# axiom_beta_plugin_module_3xPMOD.net
KiCad netlist of a schematic drawn in EAGLE
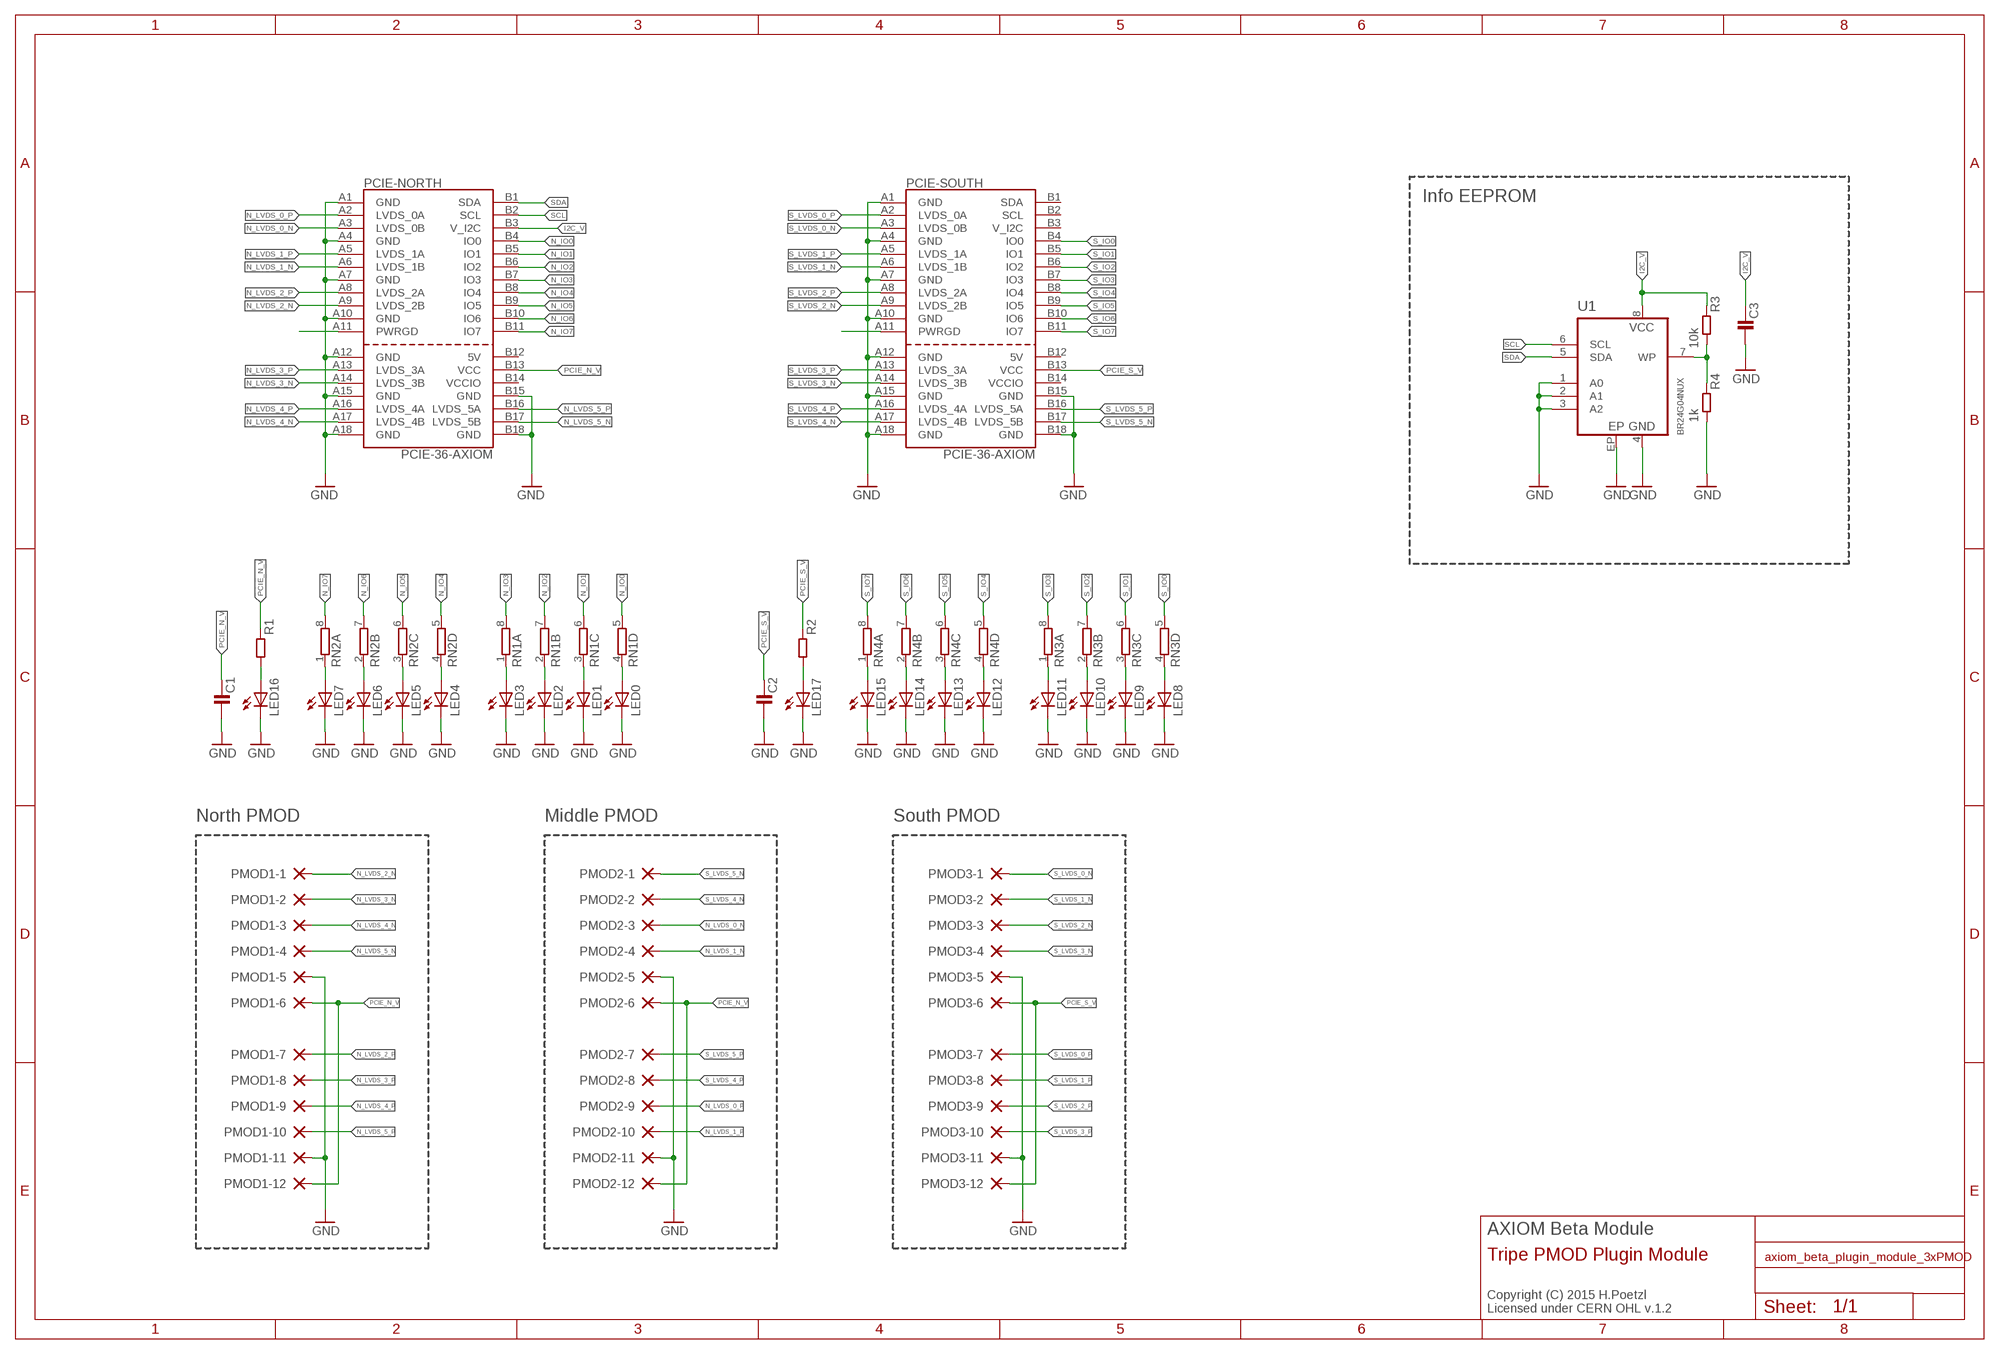
[diagram p0: schematic, sheet 1]

(export (version "E")
  (design (tool "Eeschema 10.0.6"))
  (components
    (comp (ref "C1")
      (value "C1206-A")
      (footprint "eagle-import:1206-A")
      (libsource (lib "eagle-import") (part "C1206-A"))
    )
    (comp (ref "C2")
      (value "C1206-A")
      (footprint "eagle-import:1206-A")
      (libsource (lib "eagle-import") (part "C1206-A"))
    )
    (comp (ref "C3")
      (value "C0402-B")
      (footprint "eagle-import:0402-B")
      (libsource (lib "eagle-import") (part "C0402-B"))
    )
    (comp (ref "LED0")
      (value "LEDCHIPLED_0603")
      (footprint "eagle-import:CHIPLED_0603")
      (libsource (lib "eagle-import") (part "LEDCHIPLED_0603"))
    )
    (comp (ref "LED1")
      (value "LEDCHIPLED_0603")
      (footprint "eagle-import:CHIPLED_0603")
      (libsource (lib "eagle-import") (part "LEDCHIPLED_0603"))
    )
    (comp (ref "LED2")
      (value "LEDCHIPLED_0603")
      (footprint "eagle-import:CHIPLED_0603")
      (libsource (lib "eagle-import") (part "LEDCHIPLED_0603"))
    )
    (comp (ref "LED3")
      (value "LEDCHIPLED_0603")
      (footprint "eagle-import:CHIPLED_0603")
      (libsource (lib "eagle-import") (part "LEDCHIPLED_0603"))
    )
    (comp (ref "LED4")
      (value "LEDCHIPLED_0603")
      (footprint "eagle-import:CHIPLED_0603")
      (libsource (lib "eagle-import") (part "LEDCHIPLED_0603"))
    )
    (comp (ref "LED5")
      (value "LEDCHIPLED_0603")
      (footprint "eagle-import:CHIPLED_0603")
      (libsource (lib "eagle-import") (part "LEDCHIPLED_0603"))
    )
    (comp (ref "LED6")
      (value "LEDCHIPLED_0603")
      (footprint "eagle-import:CHIPLED_0603")
      (libsource (lib "eagle-import") (part "LEDCHIPLED_0603"))
    )
    (comp (ref "LED7")
      (value "LEDCHIPLED_0603")
      (footprint "eagle-import:CHIPLED_0603")
      (libsource (lib "eagle-import") (part "LEDCHIPLED_0603"))
    )
    (comp (ref "LED8")
      (value "LEDCHIPLED_0603")
      (footprint "eagle-import:CHIPLED_0603")
      (libsource (lib "eagle-import") (part "LEDCHIPLED_0603"))
    )
    (comp (ref "LED9")
      (value "LEDCHIPLED_0603")
      (footprint "eagle-import:CHIPLED_0603")
      (libsource (lib "eagle-import") (part "LEDCHIPLED_0603"))
    )
    (comp (ref "LED10")
      (value "LEDCHIPLED_0603")
      (footprint "eagle-import:CHIPLED_0603")
      (libsource (lib "eagle-import") (part "LEDCHIPLED_0603"))
    )
    (comp (ref "LED11")
      (value "LEDCHIPLED_0603")
      (footprint "eagle-import:CHIPLED_0603")
      (libsource (lib "eagle-import") (part "LEDCHIPLED_0603"))
    )
    (comp (ref "LED12")
      (value "LEDCHIPLED_0603")
      (footprint "eagle-import:CHIPLED_0603")
      (libsource (lib "eagle-import") (part "LEDCHIPLED_0603"))
    )
    (comp (ref "LED13")
      (value "LEDCHIPLED_0603")
      (footprint "eagle-import:CHIPLED_0603")
      (libsource (lib "eagle-import") (part "LEDCHIPLED_0603"))
    )
    (comp (ref "LED14")
      (value "LEDCHIPLED_0603")
      (footprint "eagle-import:CHIPLED_0603")
      (libsource (lib "eagle-import") (part "LEDCHIPLED_0603"))
    )
    (comp (ref "LED15")
      (value "LEDCHIPLED_0603")
      (footprint "eagle-import:CHIPLED_0603")
      (libsource (lib "eagle-import") (part "LEDCHIPLED_0603"))
    )
    (comp (ref "LED16")
      (value "LEDCHIPLED_0603")
      (footprint "eagle-import:CHIPLED_0603")
      (libsource (lib "eagle-import") (part "LEDCHIPLED_0603"))
    )
    (comp (ref "LED17")
      (value "LEDCHIPLED_0603")
      (footprint "eagle-import:CHIPLED_0603")
      (libsource (lib "eagle-import") (part "LEDCHIPLED_0603"))
    )
    (comp (ref "PCIE-NORTH")
      (value "PCIE-36-AXIOM")
      (footprint "eagle-import:PCIE-36-AXIOM")
      (libsource (lib "eagle-import") (part "PCIE-36-AXIOM"))
    )
    (comp (ref "PCIE-SOUTH")
      (value "PCIE-36-AXIOM")
      (footprint "eagle-import:PCIE-36-AXIOM")
      (libsource (lib "eagle-import") (part "PCIE-36-AXIOM"))
    )
    (comp (ref "PMOD1-1")
      (value "SMD-PAD1.6X3.8MM-U")
      (footprint "eagle-import:1.6X3.8U-MM")
      (libsource (lib "eagle-import") (part "SMD-PAD1.6X3.8MM-U"))
    )
    (comp (ref "PMOD1-2")
      (value "SMD-PAD1.6X3.8MM-U")
      (footprint "eagle-import:1.6X3.8U-MM")
      (libsource (lib "eagle-import") (part "SMD-PAD1.6X3.8MM-U"))
    )
    (comp (ref "PMOD1-3")
      (value "SMD-PAD1.6X3.8MM-U")
      (footprint "eagle-import:1.6X3.8U-MM")
      (libsource (lib "eagle-import") (part "SMD-PAD1.6X3.8MM-U"))
    )
    (comp (ref "PMOD1-4")
      (value "SMD-PAD1.6X3.8MM-U")
      (footprint "eagle-import:1.6X3.8U-MM")
      (libsource (lib "eagle-import") (part "SMD-PAD1.6X3.8MM-U"))
    )
    (comp (ref "PMOD1-5")
      (value "SMD-PAD1.6X3.8MM-U")
      (footprint "eagle-import:1.6X3.8U-MM")
      (libsource (lib "eagle-import") (part "SMD-PAD1.6X3.8MM-U"))
    )
    (comp (ref "PMOD1-6")
      (value "SMD-PAD1.6X3.8MM-U")
      (footprint "eagle-import:1.6X3.8U-MM")
      (libsource (lib "eagle-import") (part "SMD-PAD1.6X3.8MM-U"))
    )
    (comp (ref "PMOD1-7")
      (value "SMD-PAD1.6X3.8MM-U")
      (footprint "eagle-import:1.6X3.8U-MM")
      (libsource (lib "eagle-import") (part "SMD-PAD1.6X3.8MM-U"))
    )
    (comp (ref "PMOD1-8")
      (value "SMD-PAD1.6X3.8MM-U")
      (footprint "eagle-import:1.6X3.8U-MM")
      (libsource (lib "eagle-import") (part "SMD-PAD1.6X3.8MM-U"))
    )
    (comp (ref "PMOD1-9")
      (value "SMD-PAD1.6X3.8MM-U")
      (footprint "eagle-import:1.6X3.8U-MM")
      (libsource (lib "eagle-import") (part "SMD-PAD1.6X3.8MM-U"))
    )
    (comp (ref "PMOD1-10")
      (value "SMD-PAD1.6X3.8MM-U")
      (footprint "eagle-import:1.6X3.8U-MM")
      (libsource (lib "eagle-import") (part "SMD-PAD1.6X3.8MM-U"))
    )
    (comp (ref "PMOD1-11")
      (value "SMD-PAD1.6X3.8MM-U")
      (footprint "eagle-import:1.6X3.8U-MM")
      (libsource (lib "eagle-import") (part "SMD-PAD1.6X3.8MM-U"))
    )
    (comp (ref "PMOD1-12")
      (value "SMD-PAD1.6X3.8MM-U")
      (footprint "eagle-import:1.6X3.8U-MM")
      (libsource (lib "eagle-import") (part "SMD-PAD1.6X3.8MM-U"))
    )
    (comp (ref "PMOD2-1")
      (value "SMD-PAD1.6X3.8MM-U")
      (footprint "eagle-import:1.6X3.8U-MM")
      (libsource (lib "eagle-import") (part "SMD-PAD1.6X3.8MM-U"))
    )
    (comp (ref "PMOD2-2")
      (value "SMD-PAD1.6X3.8MM-U")
      (footprint "eagle-import:1.6X3.8U-MM")
      (libsource (lib "eagle-import") (part "SMD-PAD1.6X3.8MM-U"))
    )
    (comp (ref "PMOD2-3")
      (value "SMD-PAD1.6X3.8MM-U")
      (footprint "eagle-import:1.6X3.8U-MM")
      (libsource (lib "eagle-import") (part "SMD-PAD1.6X3.8MM-U"))
    )
    (comp (ref "PMOD2-4")
      (value "SMD-PAD1.6X3.8MM-U")
      (footprint "eagle-import:1.6X3.8U-MM")
      (libsource (lib "eagle-import") (part "SMD-PAD1.6X3.8MM-U"))
    )
    (comp (ref "PMOD2-5")
      (value "SMD-PAD1.6X3.8MM-U")
      (footprint "eagle-import:1.6X3.8U-MM")
      (libsource (lib "eagle-import") (part "SMD-PAD1.6X3.8MM-U"))
    )
    (comp (ref "PMOD2-6")
      (value "SMD-PAD1.6X3.8MM-U")
      (footprint "eagle-import:1.6X3.8U-MM")
      (libsource (lib "eagle-import") (part "SMD-PAD1.6X3.8MM-U"))
    )
    (comp (ref "PMOD2-7")
      (value "SMD-PAD1.6X3.8MM-U")
      (footprint "eagle-import:1.6X3.8U-MM")
      (libsource (lib "eagle-import") (part "SMD-PAD1.6X3.8MM-U"))
    )
    (comp (ref "PMOD2-8")
      (value "SMD-PAD1.6X3.8MM-U")
      (footprint "eagle-import:1.6X3.8U-MM")
      (libsource (lib "eagle-import") (part "SMD-PAD1.6X3.8MM-U"))
    )
    (comp (ref "PMOD2-9")
      (value "SMD-PAD1.6X3.8MM-U")
      (footprint "eagle-import:1.6X3.8U-MM")
      (libsource (lib "eagle-import") (part "SMD-PAD1.6X3.8MM-U"))
    )
    (comp (ref "PMOD2-10")
      (value "SMD-PAD1.6X3.8MM-U")
      (footprint "eagle-import:1.6X3.8U-MM")
      (libsource (lib "eagle-import") (part "SMD-PAD1.6X3.8MM-U"))
    )
    (comp (ref "PMOD2-11")
      (value "SMD-PAD1.6X3.8MM-U")
      (footprint "eagle-import:1.6X3.8U-MM")
      (libsource (lib "eagle-import") (part "SMD-PAD1.6X3.8MM-U"))
    )
    (comp (ref "PMOD2-12")
      (value "SMD-PAD1.6X3.8MM-U")
      (footprint "eagle-import:1.6X3.8U-MM")
      (libsource (lib "eagle-import") (part "SMD-PAD1.6X3.8MM-U"))
    )
    (comp (ref "PMOD3-1")
      (value "SMD-PAD1.6X3.8MM-U")
      (footprint "eagle-import:1.6X3.8U-MM")
      (libsource (lib "eagle-import") (part "SMD-PAD1.6X3.8MM-U"))
    )
    (comp (ref "PMOD3-2")
      (value "SMD-PAD1.6X3.8MM-U")
      (footprint "eagle-import:1.6X3.8U-MM")
      (libsource (lib "eagle-import") (part "SMD-PAD1.6X3.8MM-U"))
    )
    (comp (ref "PMOD3-3")
      (value "SMD-PAD1.6X3.8MM-U")
      (footprint "eagle-import:1.6X3.8U-MM")
      (libsource (lib "eagle-import") (part "SMD-PAD1.6X3.8MM-U"))
    )
    (comp (ref "PMOD3-4")
      (value "SMD-PAD1.6X3.8MM-U")
      (footprint "eagle-import:1.6X3.8U-MM")
      (libsource (lib "eagle-import") (part "SMD-PAD1.6X3.8MM-U"))
    )
    (comp (ref "PMOD3-5")
      (value "SMD-PAD1.6X3.8MM-U")
      (footprint "eagle-import:1.6X3.8U-MM")
      (libsource (lib "eagle-import") (part "SMD-PAD1.6X3.8MM-U"))
    )
    (comp (ref "PMOD3-6")
      (value "SMD-PAD1.6X3.8MM-U")
      (footprint "eagle-import:1.6X3.8U-MM")
      (libsource (lib "eagle-import") (part "SMD-PAD1.6X3.8MM-U"))
    )
    (comp (ref "PMOD3-7")
      (value "SMD-PAD1.6X3.8MM-U")
      (footprint "eagle-import:1.6X3.8U-MM")
      (libsource (lib "eagle-import") (part "SMD-PAD1.6X3.8MM-U"))
    )
    (comp (ref "PMOD3-8")
      (value "SMD-PAD1.6X3.8MM-U")
      (footprint "eagle-import:1.6X3.8U-MM")
      (libsource (lib "eagle-import") (part "SMD-PAD1.6X3.8MM-U"))
    )
    (comp (ref "PMOD3-9")
      (value "SMD-PAD1.6X3.8MM-U")
      (footprint "eagle-import:1.6X3.8U-MM")
      (libsource (lib "eagle-import") (part "SMD-PAD1.6X3.8MM-U"))
    )
    (comp (ref "PMOD3-10")
      (value "SMD-PAD1.6X3.8MM-U")
      (footprint "eagle-import:1.6X3.8U-MM")
      (libsource (lib "eagle-import") (part "SMD-PAD1.6X3.8MM-U"))
    )
    (comp (ref "PMOD3-11")
      (value "SMD-PAD1.6X3.8MM-U")
      (footprint "eagle-import:1.6X3.8U-MM")
      (libsource (lib "eagle-import") (part "SMD-PAD1.6X3.8MM-U"))
    )
    (comp (ref "PMOD3-12")
      (value "SMD-PAD1.6X3.8MM-U")
      (footprint "eagle-import:1.6X3.8U-MM")
      (libsource (lib "eagle-import") (part "SMD-PAD1.6X3.8MM-U"))
    )
    (comp (ref "R1")
      (value "R0402-B")
      (footprint "eagle-import:0402-B")
      (libsource (lib "eagle-import") (part "R0402-B"))
    )
    (comp (ref "R2")
      (value "R0402-B")
      (footprint "eagle-import:0402-B")
      (libsource (lib "eagle-import") (part "R0402-B"))
    )
    (comp (ref "R3")
      (value "10k")
      (footprint "eagle-import:0402-B")
      (libsource (lib "eagle-import") (part "R0402-B"))
    )
    (comp (ref "R4")
      (value "1k")
      (footprint "eagle-import:0402-B")
      (libsource (lib "eagle-import") (part "R0402-B"))
    )
    (comp (ref "RN1")
      (value "4R-NCAY16")
      (footprint "eagle-import:CAY16")
      (libsource (lib "eagle-import") (part "4R-NCAY16"))
    )
    (comp (ref "RN2")
      (value "4R-NCAY16")
      (footprint "eagle-import:CAY16")
      (libsource (lib "eagle-import") (part "4R-NCAY16"))
    )
    (comp (ref "RN3")
      (value "4R-NCAY16")
      (footprint "eagle-import:CAY16")
      (libsource (lib "eagle-import") (part "4R-NCAY16"))
    )
    (comp (ref "RN4")
      (value "4R-NCAY16")
      (footprint "eagle-import:CAY16")
      (libsource (lib "eagle-import") (part "4R-NCAY16"))
    )
    (comp (ref "U1")
      (value "BR24G04NUX")
      (footprint "eagle-import:DFN200X300X100-9N")
      (libsource (lib "eagle-import") (part "BR24G04NUX"))
    )
  )
  (nets
    (net (code "1") (name "GND") (class "Default")
      (node (ref "C1") (pin "2") (pinfunction "2_2") (pintype "passive"))
      (node (ref "C2") (pin "2") (pinfunction "2_2") (pintype "passive"))
      (node (ref "C3") (pin "2") (pinfunction "2_2") (pintype "passive"))
      (node (ref "LED0") (pin "C") (pinfunction "C_C") (pintype "passive"))
      (node (ref "LED1") (pin "C") (pinfunction "C_C") (pintype "passive"))
      (node (ref "LED10") (pin "C") (pinfunction "C_C") (pintype "passive"))
      (node (ref "LED11") (pin "C") (pinfunction "C_C") (pintype "passive"))
      (node (ref "LED12") (pin "C") (pinfunction "C_C") (pintype "passive"))
      (node (ref "LED13") (pin "C") (pinfunction "C_C") (pintype "passive"))
      (node (ref "LED14") (pin "C") (pinfunction "C_C") (pintype "passive"))
      (node (ref "LED15") (pin "C") (pinfunction "C_C") (pintype "passive"))
      (node (ref "LED16") (pin "C") (pinfunction "C_C") (pintype "passive"))
      (node (ref "LED17") (pin "C") (pinfunction "C_C") (pintype "passive"))
      (node (ref "LED2") (pin "C") (pinfunction "C_C") (pintype "passive"))
      (node (ref "LED3") (pin "C") (pinfunction "C_C") (pintype "passive"))
      (node (ref "LED4") (pin "C") (pinfunction "C_C") (pintype "passive"))
      (node (ref "LED5") (pin "C") (pinfunction "C_C") (pintype "passive"))
      (node (ref "LED6") (pin "C") (pinfunction "C_C") (pintype "passive"))
      (node (ref "LED7") (pin "C") (pinfunction "C_C") (pintype "passive"))
      (node (ref "LED8") (pin "C") (pinfunction "C_C") (pintype "passive"))
      (node (ref "LED9") (pin "C") (pinfunction "C_C") (pintype "passive"))
      (node (ref "PCIE-NORTH") (pin "A1") (pinfunction "GND_A1") (pintype "passive"))
      (node (ref "PCIE-NORTH") (pin "A10") (pinfunction "GND_A10") (pintype "passive"))
      (node (ref "PCIE-NORTH") (pin "A12") (pinfunction "GND_A12") (pintype "passive"))
      (node (ref "PCIE-NORTH") (pin "A15") (pinfunction "GND_A15") (pintype "passive"))
      (node (ref "PCIE-NORTH") (pin "A18") (pinfunction "GND_A18") (pintype "passive"))
      (node (ref "PCIE-NORTH") (pin "A4") (pinfunction "GND_A4") (pintype "passive"))
      (node (ref "PCIE-NORTH") (pin "A7") (pinfunction "GND_A7") (pintype "passive"))
      (node (ref "PCIE-NORTH") (pin "B15") (pinfunction "GND_B15") (pintype "passive"))
      (node (ref "PCIE-NORTH") (pin "B18") (pinfunction "GND_B18") (pintype "passive"))
      (node (ref "PCIE-SOUTH") (pin "A1") (pinfunction "GND_A1") (pintype "passive"))
      (node (ref "PCIE-SOUTH") (pin "A10") (pinfunction "GND_A10") (pintype "passive"))
      (node (ref "PCIE-SOUTH") (pin "A12") (pinfunction "GND_A12") (pintype "passive"))
      (node (ref "PCIE-SOUTH") (pin "A15") (pinfunction "GND_A15") (pintype "passive"))
      (node (ref "PCIE-SOUTH") (pin "A18") (pinfunction "GND_A18") (pintype "passive"))
      (node (ref "PCIE-SOUTH") (pin "A4") (pinfunction "GND_A4") (pintype "passive"))
      (node (ref "PCIE-SOUTH") (pin "A7") (pinfunction "GND_A7") (pintype "passive"))
      (node (ref "PCIE-SOUTH") (pin "B15") (pinfunction "GND_B15") (pintype "passive"))
      (node (ref "PCIE-SOUTH") (pin "B18") (pinfunction "GND_B18") (pintype "passive"))
      (node (ref "PMOD1-11") (pin "1") (pinfunction "P_1") (pintype "passive"))
      (node (ref "PMOD1-5") (pin "1") (pinfunction "P_1") (pintype "passive"))
      (node (ref "PMOD2-11") (pin "1") (pinfunction "P_1") (pintype "passive"))
      (node (ref "PMOD2-5") (pin "1") (pinfunction "P_1") (pintype "passive"))
      (node (ref "PMOD3-11") (pin "1") (pinfunction "P_1") (pintype "passive"))
      (node (ref "PMOD3-5") (pin "1") (pinfunction "P_1") (pintype "passive"))
      (node (ref "R4") (pin "2") (pinfunction "2_2") (pintype "passive"))
      (node (ref "U1") (pin "1") (pinfunction "A0_1") (pintype "input"))
      (node (ref "U1") (pin "2") (pinfunction "A1_2") (pintype "input"))
      (node (ref "U1") (pin "3") (pinfunction "A2_3") (pintype "input"))
      (node (ref "U1") (pin "4") (pinfunction "GND_4") (pintype "passive"))
      (node (ref "U1") (pin "EP") (pinfunction "EP_EP") (pintype "passive"))
    )
    (net (code "2") (name "I2C_V") (class "Default")
      (node (ref "C3") (pin "1") (pinfunction "1_1") (pintype "passive"))
      (node (ref "PCIE-NORTH") (pin "B3") (pinfunction "V_I2C_B3") (pintype "passive"))
      (node (ref "R3") (pin "1") (pinfunction "1_1") (pintype "passive"))
      (node (ref "U1") (pin "8") (pinfunction "VCC_8") (pintype "power_in"))
    )
    (net (code "3") (name "N_IO0") (class "Default")
      (node (ref "PCIE-NORTH") (pin "B4") (pinfunction "IO0_B4") (pintype "passive"))
      (node (ref "RN1") (pin "5") (pinfunction "2_5") (pintype "passive"))
    )
    (net (code "4") (name "N_IO1") (class "Default")
      (node (ref "PCIE-NORTH") (pin "B5") (pinfunction "IO1_B5") (pintype "passive"))
      (node (ref "RN1") (pin "6") (pinfunction "2_6") (pintype "passive"))
    )
    (net (code "5") (name "N_IO2") (class "Default")
      (node (ref "PCIE-NORTH") (pin "B6") (pinfunction "IO2_B6") (pintype "passive"))
      (node (ref "RN1") (pin "7") (pinfunction "2_7") (pintype "passive"))
    )
    (net (code "6") (name "N_IO3") (class "Default")
      (node (ref "PCIE-NORTH") (pin "B7") (pinfunction "IO3_B7") (pintype "passive"))
      (node (ref "RN1") (pin "8") (pinfunction "2_8") (pintype "passive"))
    )
    (net (code "7") (name "N_IO4") (class "Default")
      (node (ref "PCIE-NORTH") (pin "B8") (pinfunction "IO4_B8") (pintype "passive"))
      (node (ref "RN2") (pin "5") (pinfunction "2_5") (pintype "passive"))
    )
    (net (code "8") (name "N_IO5") (class "Default")
      (node (ref "PCIE-NORTH") (pin "B9") (pinfunction "IO5_B9") (pintype "passive"))
      (node (ref "RN2") (pin "6") (pinfunction "2_6") (pintype "passive"))
    )
    (net (code "9") (name "N_IO6") (class "Default")
      (node (ref "PCIE-NORTH") (pin "B10") (pinfunction "IO6_B10") (pintype "passive"))
      (node (ref "RN2") (pin "7") (pinfunction "2_7") (pintype "passive"))
    )
    (net (code "10") (name "N_IO7") (class "Default")
      (node (ref "PCIE-NORTH") (pin "B11") (pinfunction "IO7_B11") (pintype "passive"))
      (node (ref "RN2") (pin "8") (pinfunction "2_8") (pintype "passive"))
    )
    (net (code "11") (name "N_LVDS_0_N") (class "Default")
      (node (ref "PCIE-NORTH") (pin "A3") (pinfunction "LVDS_0B_A3") (pintype "passive"))
      (node (ref "PMOD2-3") (pin "1") (pinfunction "P_1") (pintype "passive"))
    )
    (net (code "12") (name "N_LVDS_0_P") (class "Default")
      (node (ref "PCIE-NORTH") (pin "A2") (pinfunction "LVDS_0A_A2") (pintype "passive"))
      (node (ref "PMOD2-9") (pin "1") (pinfunction "P_1") (pintype "passive"))
    )
    (net (code "13") (name "N_LVDS_1_N") (class "Default")
      (node (ref "PCIE-NORTH") (pin "A6") (pinfunction "LVDS_1B_A6") (pintype "passive"))
      (node (ref "PMOD2-4") (pin "1") (pinfunction "P_1") (pintype "passive"))
    )
    (net (code "14") (name "N_LVDS_1_P") (class "Default")
      (node (ref "PCIE-NORTH") (pin "A5") (pinfunction "LVDS_1A_A5") (pintype "passive"))
      (node (ref "PMOD2-10") (pin "1") (pinfunction "P_1") (pintype "passive"))
    )
    (net (code "15") (name "N_LVDS_2_N") (class "Default")
      (node (ref "PCIE-NORTH") (pin "A9") (pinfunction "LVDS_2B_A9") (pintype "passive"))
      (node (ref "PMOD1-1") (pin "1") (pinfunction "P_1") (pintype "passive"))
    )
    (net (code "16") (name "N_LVDS_2_P") (class "Default")
      (node (ref "PCIE-NORTH") (pin "A8") (pinfunction "LVDS_2A_A8") (pintype "passive"))
      (node (ref "PMOD1-7") (pin "1") (pinfunction "P_1") (pintype "passive"))
    )
    (net (code "17") (name "N_LVDS_3_N") (class "Default")
      (node (ref "PCIE-NORTH") (pin "A14") (pinfunction "LVDS_3B_A14") (pintype "passive"))
      (node (ref "PMOD1-2") (pin "1") (pinfunction "P_1") (pintype "passive"))
    )
    (net (code "18") (name "N_LVDS_3_P") (class "Default")
      (node (ref "PCIE-NORTH") (pin "A13") (pinfunction "LVDS_3A_A13") (pintype "passive"))
      (node (ref "PMOD1-8") (pin "1") (pinfunction "P_1") (pintype "passive"))
    )
    (net (code "19") (name "N_LVDS_4_N") (class "Default")
      (node (ref "PCIE-NORTH") (pin "A17") (pinfunction "LVDS_4B_A17") (pintype "passive"))
      (node (ref "PMOD1-3") (pin "1") (pinfunction "P_1") (pintype "passive"))
    )
    (net (code "20") (name "N_LVDS_4_P") (class "Default")
      (node (ref "PCIE-NORTH") (pin "A16") (pinfunction "LVDS_4A_A16") (pintype "passive"))
      (node (ref "PMOD1-9") (pin "1") (pinfunction "P_1") (pintype "passive"))
    )
    (net (code "21") (name "N_LVDS_5_N") (class "Default")
      (node (ref "PCIE-NORTH") (pin "B17") (pinfunction "LVDS_5B_B17") (pintype "passive"))
      (node (ref "PMOD1-4") (pin "1") (pinfunction "P_1") (pintype "passive"))
    )
    (net (code "22") (name "N_LVDS_5_P") (class "Default")
      (node (ref "PCIE-NORTH") (pin "B16") (pinfunction "LVDS_5A_B16") (pintype "passive"))
      (node (ref "PMOD1-10") (pin "1") (pinfunction "P_1") (pintype "passive"))
    )
    (net (code "23") (name "Net-(LED3-PadA)") (class "Default")
      (node (ref "LED3") (pin "A") (pinfunction "A_A") (pintype "passive"))
      (node (ref "RN1") (pin "1") (pinfunction "1_1") (pintype "passive"))
    )
    (net (code "24") (name "Net-(LED7-PadA)") (class "Default")
      (node (ref "LED7") (pin "A") (pinfunction "A_A") (pintype "passive"))
      (node (ref "RN2") (pin "1") (pinfunction "1_1") (pintype "passive"))
    )
    (net (code "25") (name "Net-(LED11-PadA)") (class "Default")
      (node (ref "LED11") (pin "A") (pinfunction "A_A") (pintype "passive"))
      (node (ref "RN3") (pin "1") (pinfunction "1_1") (pintype "passive"))
    )
    (net (code "26") (name "Net-(LED15-PadA)") (class "Default")
      (node (ref "LED15") (pin "A") (pinfunction "A_A") (pintype "passive"))
      (node (ref "RN4") (pin "1") (pinfunction "1_1") (pintype "passive"))
    )
    (net (code "27") (name "Net-(LED16-PadA)") (class "Default")
      (node (ref "LED16") (pin "A") (pinfunction "A_A") (pintype "passive"))
      (node (ref "R1") (pin "2") (pinfunction "2_2") (pintype "passive"))
    )
    (net (code "28") (name "Net-(LED17-PadA)") (class "Default")
      (node (ref "LED17") (pin "A") (pinfunction "A_A") (pintype "passive"))
      (node (ref "R2") (pin "2") (pinfunction "2_2") (pintype "passive"))
    )
    (net (code "29") (name "Net-(RN1B-1)") (class "Default")
      (node (ref "LED2") (pin "A") (pinfunction "A_A") (pintype "passive"))
      (node (ref "RN1") (pin "2") (pinfunction "1_2") (pintype "passive"))
    )
    (net (code "30") (name "Net-(RN1C-1)") (class "Default")
      (node (ref "LED1") (pin "A") (pinfunction "A_A") (pintype "passive"))
      (node (ref "RN1") (pin "3") (pinfunction "1_3") (pintype "passive"))
    )
    (net (code "31") (name "Net-(RN1D-1)") (class "Default")
      (node (ref "LED0") (pin "A") (pinfunction "A_A") (pintype "passive"))
      (node (ref "RN1") (pin "4") (pinfunction "1_4") (pintype "passive"))
    )
    (net (code "32") (name "Net-(RN2B-1)") (class "Default")
      (node (ref "LED6") (pin "A") (pinfunction "A_A") (pintype "passive"))
      (node (ref "RN2") (pin "2") (pinfunction "1_2") (pintype "passive"))
    )
    (net (code "33") (name "Net-(RN2C-1)") (class "Default")
      (node (ref "LED5") (pin "A") (pinfunction "A_A") (pintype "passive"))
      (node (ref "RN2") (pin "3") (pinfunction "1_3") (pintype "passive"))
    )
    (net (code "34") (name "Net-(RN2D-1)") (class "Default")
      (node (ref "LED4") (pin "A") (pinfunction "A_A") (pintype "passive"))
      (node (ref "RN2") (pin "4") (pinfunction "1_4") (pintype "passive"))
    )
    (net (code "35") (name "Net-(RN3B-1)") (class "Default")
      (node (ref "LED10") (pin "A") (pinfunction "A_A") (pintype "passive"))
      (node (ref "RN3") (pin "2") (pinfunction "1_2") (pintype "passive"))
    )
    (net (code "36") (name "Net-(RN3C-1)") (class "Default")
      (node (ref "LED9") (pin "A") (pinfunction "A_A") (pintype "passive"))
      (node (ref "RN3") (pin "3") (pinfunction "1_3") (pintype "passive"))
    )
    (net (code "37") (name "Net-(RN3D-1)") (class "Default")
      (node (ref "LED8") (pin "A") (pinfunction "A_A") (pintype "passive"))
      (node (ref "RN3") (pin "4") (pinfunction "1_4") (pintype "passive"))
    )
    (net (code "38") (name "Net-(RN4B-1)") (class "Default")
      (node (ref "LED14") (pin "A") (pinfunction "A_A") (pintype "passive"))
      (node (ref "RN4") (pin "2") (pinfunction "1_2") (pintype "passive"))
    )
    (net (code "39") (name "Net-(RN4C-1)") (class "Default")
      (node (ref "LED13") (pin "A") (pinfunction "A_A") (pintype "passive"))
      (node (ref "RN4") (pin "3") (pinfunction "1_3") (pintype "passive"))
    )
    (net (code "40") (name "Net-(RN4D-1)") (class "Default")
      (node (ref "LED12") (pin "A") (pinfunction "A_A") (pintype "passive"))
      (node (ref "RN4") (pin "4") (pinfunction "1_4") (pintype "passive"))
    )
    (net (code "41") (name "Net-(U1-WP)") (class "Default")
      (node (ref "R3") (pin "2") (pinfunction "2_2") (pintype "passive"))
      (node (ref "R4") (pin "1") (pinfunction "1_1") (pintype "passive"))
      (node (ref "U1") (pin "7") (pinfunction "WP_7") (pintype "input"))
    )
    (net (code "42") (name "PCIE_N_V") (class "Default")
      (node (ref "C1") (pin "1") (pinfunction "1_1") (pintype "passive"))
      (node (ref "PCIE-NORTH") (pin "B13") (pinfunction "VCC_B13") (pintype "passive"))
      (node (ref "PMOD1-12") (pin "1") (pinfunction "P_1") (pintype "passive"))
      (node (ref "PMOD1-6") (pin "1") (pinfunction "P_1") (pintype "passive"))
      (node (ref "PMOD2-12") (pin "1") (pinfunction "P_1") (pintype "passive"))
      (node (ref "PMOD2-6") (pin "1") (pinfunction "P_1") (pintype "passive"))
      (node (ref "R1") (pin "1") (pinfunction "1_1") (pintype "passive"))
    )
    (net (code "43") (name "PCIE_S_V") (class "Default")
      (node (ref "C2") (pin "1") (pinfunction "1_1") (pintype "passive"))
      (node (ref "PCIE-SOUTH") (pin "B13") (pinfunction "VCC_B13") (pintype "passive"))
      (node (ref "PMOD3-12") (pin "1") (pinfunction "P_1") (pintype "passive"))
      (node (ref "PMOD3-6") (pin "1") (pinfunction "P_1") (pintype "passive"))
      (node (ref "R2") (pin "1") (pinfunction "1_1") (pintype "passive"))
    )
    (net (code "44") (name "SCL") (class "Default")
      (node (ref "PCIE-NORTH") (pin "B2") (pinfunction "SCL_B2") (pintype "passive"))
      (node (ref "U1") (pin "6") (pinfunction "SCL_6") (pintype "input"))
    )
    (net (code "45") (name "SDA") (class "Default")
      (node (ref "PCIE-NORTH") (pin "B1") (pinfunction "SDA_B1") (pintype "passive"))
      (node (ref "U1") (pin "5") (pinfunction "SDA_5") (pintype "bidirectional"))
    )
    (net (code "46") (name "S_IO0") (class "Default")
      (node (ref "PCIE-SOUTH") (pin "B4") (pinfunction "IO0_B4") (pintype "passive"))
      (node (ref "RN3") (pin "5") (pinfunction "2_5") (pintype "passive"))
    )
    (net (code "47") (name "S_IO1") (class "Default")
      (node (ref "PCIE-SOUTH") (pin "B5") (pinfunction "IO1_B5") (pintype "passive"))
      (node (ref "RN3") (pin "6") (pinfunction "2_6") (pintype "passive"))
    )
    (net (code "48") (name "S_IO2") (class "Default")
      (node (ref "PCIE-SOUTH") (pin "B6") (pinfunction "IO2_B6") (pintype "passive"))
      (node (ref "RN3") (pin "7") (pinfunction "2_7") (pintype "passive"))
    )
    (net (code "49") (name "S_IO3") (class "Default")
      (node (ref "PCIE-SOUTH") (pin "B7") (pinfunction "IO3_B7") (pintype "passive"))
      (node (ref "RN3") (pin "8") (pinfunction "2_8") (pintype "passive"))
    )
    (net (code "50") (name "S_IO4") (class "Default")
      (node (ref "PCIE-SOUTH") (pin "B8") (pinfunction "IO4_B8") (pintype "passive"))
      (node (ref "RN4") (pin "5") (pinfunction "2_5") (pintype "passive"))
    )
    (net (code "51") (name "S_IO5") (class "Default")
      (node (ref "PCIE-SOUTH") (pin "B9") (pinfunction "IO5_B9") (pintype "passive"))
      (node (ref "RN4") (pin "6") (pinfunction "2_6") (pintype "passive"))
    )
    (net (code "52") (name "S_IO6") (class "Default")
      (node (ref "PCIE-SOUTH") (pin "B10") (pinfunction "IO6_B10") (pintype "passive"))
      (node (ref "RN4") (pin "7") (pinfunction "2_7") (pintype "passive"))
    )
    (net (code "53") (name "S_IO7") (class "Default")
      (node (ref "PCIE-SOUTH") (pin "B11") (pinfunction "IO7_B11") (pintype "passive"))
      (node (ref "RN4") (pin "8") (pinfunction "2_8") (pintype "passive"))
    )
    (net (code "54") (name "S_LVDS_0_N") (class "Default")
      (node (ref "PCIE-SOUTH") (pin "A3") (pinfunction "LVDS_0B_A3") (pintype "passive"))
      (node (ref "PMOD3-1") (pin "1") (pinfunction "P_1") (pintype "passive"))
    )
    (net (code "55") (name "S_LVDS_0_P") (class "Default")
      (node (ref "PCIE-SOUTH") (pin "A2") (pinfunction "LVDS_0A_A2") (pintype "passive"))
      (node (ref "PMOD3-7") (pin "1") (pinfunction "P_1") (pintype "passive"))
    )
    (net (code "56") (name "S_LVDS_1_N") (class "Default")
      (node (ref "PCIE-SOUTH") (pin "A6") (pinfunction "LVDS_1B_A6") (pintype "passive"))
      (node (ref "PMOD3-2") (pin "1") (pinfunction "P_1") (pintype "passive"))
    )
    (net (code "57") (name "S_LVDS_1_P") (class "Default")
      (node (ref "PCIE-SOUTH") (pin "A5") (pinfunction "LVDS_1A_A5") (pintype "passive"))
      (node (ref "PMOD3-8") (pin "1") (pinfunction "P_1") (pintype "passive"))
    )
    (net (code "58") (name "S_LVDS_2_N") (class "Default")
      (node (ref "PCIE-SOUTH") (pin "A9") (pinfunction "LVDS_2B_A9") (pintype "passive"))
      (node (ref "PMOD3-3") (pin "1") (pinfunction "P_1") (pintype "passive"))
    )
    (net (code "59") (name "S_LVDS_2_P") (class "Default")
      (node (ref "PCIE-SOUTH") (pin "A8") (pinfunction "LVDS_2A_A8") (pintype "passive"))
      (node (ref "PMOD3-9") (pin "1") (pinfunction "P_1") (pintype "passive"))
    )
    (net (code "60") (name "S_LVDS_3_N") (class "Default")
      (node (ref "PCIE-SOUTH") (pin "A14") (pinfunction "LVDS_3B_A14") (pintype "passive"))
      (node (ref "PMOD3-4") (pin "1") (pinfunction "P_1") (pintype "passive"))
    )
    (net (code "61") (name "S_LVDS_3_P") (class "Default")
      (node (ref "PCIE-SOUTH") (pin "A13") (pinfunction "LVDS_3A_A13") (pintype "passive"))
      (node (ref "PMOD3-10") (pin "1") (pinfunction "P_1") (pintype "passive"))
    )
    (net (code "62") (name "S_LVDS_4_N") (class "Default")
      (node (ref "PCIE-SOUTH") (pin "A17") (pinfunction "LVDS_4B_A17") (pintype "passive"))
      (node (ref "PMOD2-2") (pin "1") (pinfunction "P_1") (pintype "passive"))
    )
    (net (code "63") (name "S_LVDS_4_P") (class "Default")
      (node (ref "PCIE-SOUTH") (pin "A16") (pinfunction "LVDS_4A_A16") (pintype "passive"))
      (node (ref "PMOD2-8") (pin "1") (pinfunction "P_1") (pintype "passive"))
    )
    (net (code "64") (name "S_LVDS_5_N") (class "Default")
      (node (ref "PCIE-SOUTH") (pin "B17") (pinfunction "LVDS_5B_B17") (pintype "passive"))
      (node (ref "PMOD2-1") (pin "1") (pinfunction "P_1") (pintype "passive"))
    )
    (net (code "65") (name "S_LVDS_5_P") (class "Default")
      (node (ref "PCIE-SOUTH") (pin "B16") (pinfunction "LVDS_5A_B16") (pintype "passive"))
      (node (ref "PMOD2-7") (pin "1") (pinfunction "P_1") (pintype "passive"))
    )
    (net (code "66") (name "unconnected-(PCIE-NORTH-5V-PadB12)") (class "Default")
      (node (ref "PCIE-NORTH") (pin "B12") (pinfunction "5V_B12") (pintype "passive"))
    )
    (net (code "67") (name "unconnected-(PCIE-NORTH-PWRGD-PadA11)") (class "Default")
      (node (ref "PCIE-NORTH") (pin "A11") (pinfunction "PWRGD_A11") (pintype "passive"))
    )
    (net (code "68") (name "unconnected-(PCIE-NORTH-VCCIO-PadB14)") (class "Default")
      (node (ref "PCIE-NORTH") (pin "B14") (pinfunction "VCCIO_B14") (pintype "passive"))
    )
    (net (code "69") (name "unconnected-(PCIE-SOUTH-5V-PadB12)") (class "Default")
      (node (ref "PCIE-SOUTH") (pin "B12") (pinfunction "5V_B12") (pintype "passive"))
    )
    (net (code "70") (name "unconnected-(PCIE-SOUTH-PWRGD-PadA11)") (class "Default")
      (node (ref "PCIE-SOUTH") (pin "A11") (pinfunction "PWRGD_A11") (pintype "passive"))
    )
    (net (code "71") (name "unconnected-(PCIE-SOUTH-SCL-PadB2)") (class "Default")
      (node (ref "PCIE-SOUTH") (pin "B2") (pinfunction "SCL_B2") (pintype "passive"))
    )
    (net (code "72") (name "unconnected-(PCIE-SOUTH-SDA-PadB1)") (class "Default")
      (node (ref "PCIE-SOUTH") (pin "B1") (pinfunction "SDA_B1") (pintype "passive"))
    )
    (net (code "73") (name "unconnected-(PCIE-SOUTH-VCCIO-PadB14)") (class "Default")
      (node (ref "PCIE-SOUTH") (pin "B14") (pinfunction "VCCIO_B14") (pintype "passive"))
    )
    (net (code "74") (name "unconnected-(PCIE-SOUTH-V_I2C-PadB3)") (class "Default")
      (node (ref "PCIE-SOUTH") (pin "B3") (pinfunction "V_I2C_B3") (pintype "passive"))
    )
  )
)
